# VA-Meter-I2C.net
KiCad netlist of a schematic drawn in EAGLE
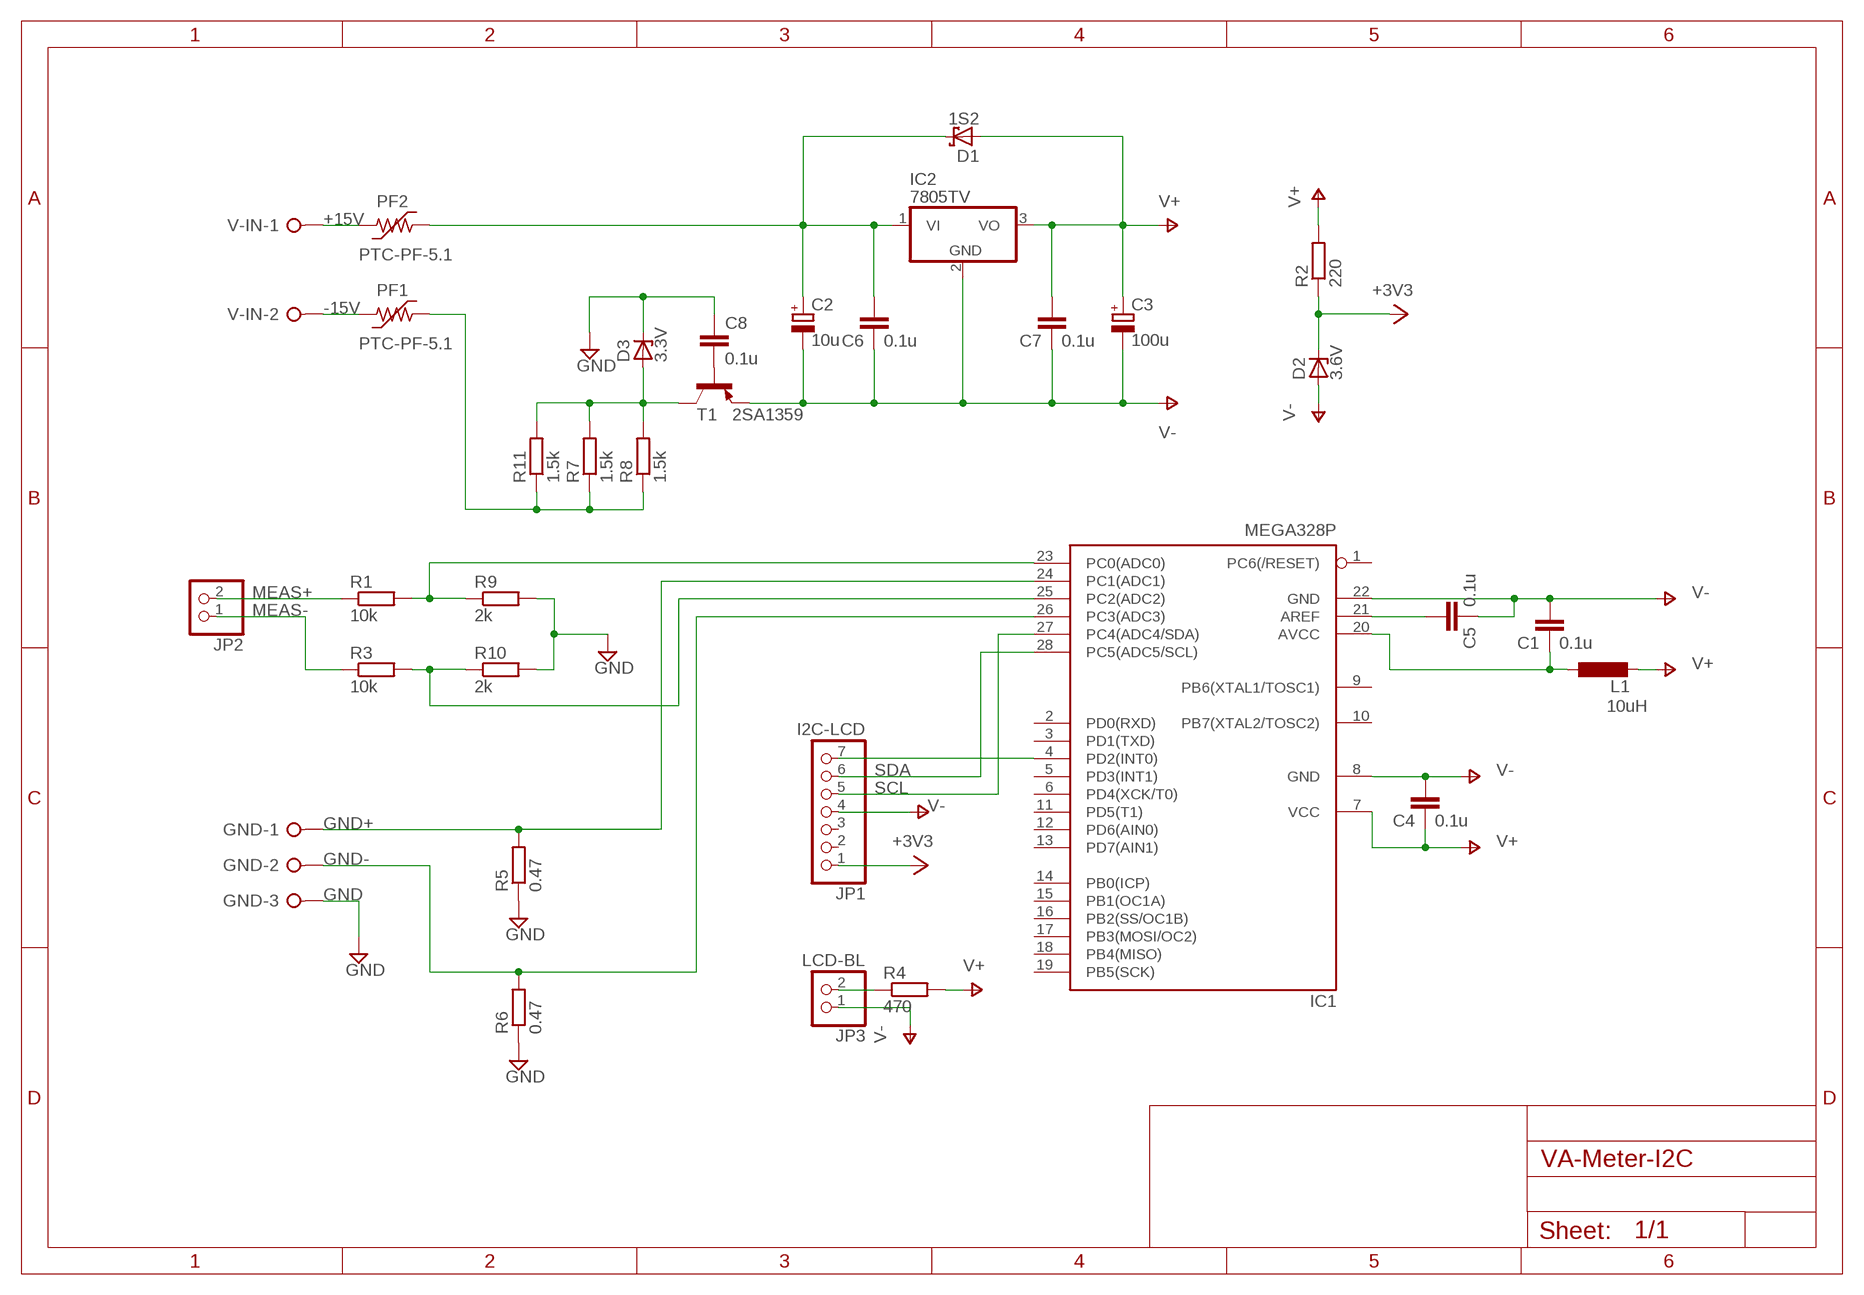
[diagram p0: schematic, sheet 1]

(export (version "E")
  (design (tool "Eeschema 10.0.6"))
  (components
    (comp (ref "C1")
      (value "0.1u")
      (footprint "eagle-import:C050-024X044")
      (libsource (lib "eagle-import") (part "C-EU050-024X044"))
    )
    (comp (ref "C2")
      (value "10u")
      (footprint "eagle-import:E2,5-5")
      (libsource (lib "eagle-import") (part "CPOL-EUE2.5-5"))
    )
    (comp (ref "C3")
      (value "100u")
      (footprint "eagle-import:E2,5-6")
      (libsource (lib "eagle-import") (part "CPOL-EUE2.5-6"))
    )
    (comp (ref "C4")
      (value "0.1u")
      (footprint "eagle-import:C050-024X044")
      (libsource (lib "eagle-import") (part "C-EU050-024X044"))
    )
    (comp (ref "C5")
      (value "0.1u")
      (footprint "eagle-import:C050-024X044")
      (libsource (lib "eagle-import") (part "C-EU050-024X044"))
    )
    (comp (ref "C6")
      (value "0.1u")
      (footprint "eagle-import:C050-024X044")
      (libsource (lib "eagle-import") (part "C-EU050-024X044"))
    )
    (comp (ref "C7")
      (value "0.1u")
      (footprint "eagle-import:C050-024X044")
      (libsource (lib "eagle-import") (part "C-EU050-024X044"))
    )
    (comp (ref "C8")
      (value "0.1u")
      (footprint "eagle-import:C050-024X044")
      (libsource (lib "eagle-import") (part "C-EU050-024X044"))
    )
    (comp (ref "D1")
      (value "1S2")
      (footprint "eagle-import:CB417-15")
      (libsource (lib "eagle-import") (part "SCHOTTKY-DIODECB417-15"))
    )
    (comp (ref "D2")
      (value "3.6V")
      (footprint "eagle-import:ZDIO-5")
      (libsource (lib "eagle-import") (part "ZENER-DIODEZD-5"))
    )
    (comp (ref "D3")
      (value "3.3V")
      (footprint "eagle-import:ZDIO-5")
      (libsource (lib "eagle-import") (part "ZENER-DIODEZD-5"))
    )
    (comp (ref "GND")
      (value "W237-03P")
      (footprint "eagle-import:W237-133")
      (libsource (lib "eagle-import") (part "W237-03P"))
    )
    (comp (ref "IC1")
      (value "MEGA328P")
      (footprint "eagle-import:MEGA328P")
      (libsource (lib "eagle-import") (part "MEGA328P"))
    )
    (comp (ref "IC2")
      (value "7805TV")
      (footprint "eagle-import:TO220V")
      (libsource (lib "eagle-import") (part "78TV05"))
    )
    (comp (ref "JP1")
      (value "I2C-LCD")
      (footprint "eagle-import:1X07")
      (libsource (lib "eagle-import") (part "PINHD-1X7"))
    )
    (comp (ref "JP2")
      (value "PINHD-1X2")
      (footprint "eagle-import:1X02")
      (libsource (lib "eagle-import") (part "PINHD-1X2"))
    )
    (comp (ref "JP3")
      (value "LCD-BL")
      (footprint "eagle-import:1X02")
      (libsource (lib "eagle-import") (part "PINHD-1X2"))
    )
    (comp (ref "L1")
      (value "10uH")
      (footprint "eagle-import:6000-XXXX-RC")
      (libsource (lib "eagle-import") (part "L-EU6000-XXX-RC"))
    )
    (comp (ref "PF1")
      (value "PTC-PF-5.1")
      (footprint "eagle-import:PF-5.1")
      (libsource (lib "eagle-import") (part "PTC-PF-5.1"))
    )
    (comp (ref "PF2")
      (value "PTC-PF-5.1")
      (footprint "eagle-import:PF-5.1")
      (libsource (lib "eagle-import") (part "PTC-PF-5.1"))
    )
    (comp (ref "R1")
      (value "10k")
      (footprint "eagle-import:0207_7")
      (libsource (lib "eagle-import") (part "R-EU_0207/7"))
    )
    (comp (ref "R2")
      (value "220")
      (footprint "eagle-import:0207_7")
      (libsource (lib "eagle-import") (part "R-EU_0207/7"))
    )
    (comp (ref "R3")
      (value "10k")
      (footprint "eagle-import:0207_7")
      (libsource (lib "eagle-import") (part "R-EU_0207/7"))
    )
    (comp (ref "R4")
      (value "470")
      (footprint "eagle-import:0207_7")
      (libsource (lib "eagle-import") (part "R-EU_0207/7"))
    )
    (comp (ref "R5")
      (value "0.47")
      (footprint "eagle-import:P0613_15")
      (libsource (lib "eagle-import") (part "R-EU_0613/15"))
    )
    (comp (ref "R6")
      (value "0.47")
      (footprint "eagle-import:P0613_15")
      (libsource (lib "eagle-import") (part "R-EU_0613/15"))
    )
    (comp (ref "R7")
      (value "1.5k")
      (footprint "eagle-import:P0613_15")
      (libsource (lib "eagle-import") (part "R-EU_0613/15"))
    )
    (comp (ref "R8")
      (value "1.5k")
      (footprint "eagle-import:P0613_15")
      (libsource (lib "eagle-import") (part "R-EU_0613/15"))
    )
    (comp (ref "R9")
      (value "2k")
      (footprint "eagle-import:0207_7")
      (libsource (lib "eagle-import") (part "R-EU_0207/7"))
    )
    (comp (ref "R10")
      (value "2k")
      (footprint "eagle-import:0207_7")
      (libsource (lib "eagle-import") (part "R-EU_0207/7"))
    )
    (comp (ref "R11")
      (value "1.5k")
      (footprint "eagle-import:P0613_15")
      (libsource (lib "eagle-import") (part "R-EU_0613/15"))
    )
    (comp (ref "T1")
      (value "2SA1359")
      (footprint "eagle-import:TO126V")
      (libsource (lib "eagle-import") (part "-PNP-TO126V"))
    )
    (comp (ref "V-IN")
      (value "W237-02P")
      (footprint "eagle-import:W237-132")
      (libsource (lib "eagle-import") (part "W237-02P"))
    )
  )
  (nets
    (net (code "1") (name "+3V3") (class "Default")
      (node (ref "D2") (pin "C") (pinfunction "C_C") (pintype "passive"))
      (node (ref "JP1") (pin "1") (pinfunction "1_1") (pintype "passive"))
      (node (ref "R2") (pin "1") (pinfunction "1_1") (pintype "passive"))
    )
    (net (code "2") (name "/+15V") (class "Default")
      (node (ref "C2") (pin "+") (pinfunction "+_+") (pintype "passive"))
      (node (ref "C6") (pin "2") (pinfunction "2_2") (pintype "passive"))
      (node (ref "D1") (pin "C") (pinfunction "C_C") (pintype "passive"))
      (node (ref "IC2") (pin "1") (pinfunction "VI_1") (pintype "input"))
      (node (ref "PF2") (pin "2") (pinfunction "2_2") (pintype "passive"))
    )
    (net (code "3") (name "/-15V") (class "Default")
      (node (ref "PF1") (pin "2") (pinfunction "2_2") (pintype "passive"))
      (node (ref "R11") (pin "1") (pinfunction "1_1") (pintype "passive"))
      (node (ref "R7") (pin "1") (pinfunction "1_1") (pintype "passive"))
      (node (ref "R8") (pin "1") (pinfunction "1_1") (pintype "passive"))
    )
    (net (code "4") (name "/GND+") (class "Default")
      (node (ref "GND") (pin "1") (pinfunction "KL_1") (pintype "passive"))
      (node (ref "IC1") (pin "24") (pinfunction "PC1(ADC1)_24") (pintype "bidirectional"))
      (node (ref "R5") (pin "2") (pinfunction "2_2") (pintype "passive"))
    )
    (net (code "5") (name "/GND-") (class "Default")
      (node (ref "GND") (pin "2") (pinfunction "KL_2") (pintype "passive"))
      (node (ref "IC1") (pin "26") (pinfunction "PC3(ADC3)_26") (pintype "bidirectional"))
      (node (ref "R6") (pin "2") (pinfunction "2_2") (pintype "passive"))
    )
    (net (code "6") (name "/MEAS+") (class "Default")
      (node (ref "JP2") (pin "2") (pinfunction "2_2") (pintype "passive"))
      (node (ref "R1") (pin "1") (pinfunction "1_1") (pintype "passive"))
    )
    (net (code "7") (name "/MEAS-") (class "Default")
      (node (ref "JP2") (pin "1") (pinfunction "1_1") (pintype "passive"))
      (node (ref "R3") (pin "1") (pinfunction "1_1") (pintype "passive"))
    )
    (net (code "8") (name "/SCL") (class "Default")
      (node (ref "IC1") (pin "27") (pinfunction "PC4(ADC4/SDA)_27") (pintype "bidirectional"))
      (node (ref "JP1") (pin "5") (pinfunction "5_5") (pintype "passive"))
    )
    (net (code "9") (name "/SDA") (class "Default")
      (node (ref "IC1") (pin "28") (pinfunction "PC5(ADC5/SCL)_28") (pintype "bidirectional"))
      (node (ref "JP1") (pin "6") (pinfunction "6_6") (pintype "passive"))
    )
    (net (code "10") (name "GND") (class "Default")
      (node (ref "C8") (pin "1") (pinfunction "1_1") (pintype "passive"))
      (node (ref "D3") (pin "C") (pinfunction "C_C") (pintype "passive"))
      (node (ref "GND") (pin "3") (pinfunction "KL_3") (pintype "passive"))
      (node (ref "R10") (pin "2") (pinfunction "2_2") (pintype "passive"))
      (node (ref "R5") (pin "1") (pinfunction "1_1") (pintype "passive"))
      (node (ref "R6") (pin "1") (pinfunction "1_1") (pintype "passive"))
      (node (ref "R9") (pin "2") (pinfunction "2_2") (pintype "passive"))
    )
    (net (code "11") (name "Net-(IC1-AREF)") (class "Default")
      (node (ref "C5") (pin "2") (pinfunction "2_2") (pintype "passive"))
      (node (ref "IC1") (pin "21") (pinfunction "AREF_21") (pintype "passive"))
    )
    (net (code "12") (name "Net-(IC1-AVCC)") (class "Default")
      (node (ref "C1") (pin "1") (pinfunction "1_1") (pintype "passive"))
      (node (ref "IC1") (pin "20") (pinfunction "AVCC_20") (pintype "power_in"))
      (node (ref "L1") (pin "1") (pinfunction "1_1") (pintype "passive"))
    )
    (net (code "13") (name "Net-(IC1-PC0(ADC0))") (class "Default")
      (node (ref "IC1") (pin "23") (pinfunction "PC0(ADC0)_23") (pintype "bidirectional"))
      (node (ref "R1") (pin "2") (pinfunction "2_2") (pintype "passive"))
      (node (ref "R9") (pin "1") (pinfunction "1_1") (pintype "passive"))
    )
    (net (code "14") (name "Net-(IC1-PC2(ADC2))") (class "Default")
      (node (ref "IC1") (pin "25") (pinfunction "PC2(ADC2)_25") (pintype "bidirectional"))
      (node (ref "R10") (pin "1") (pinfunction "1_1") (pintype "passive"))
      (node (ref "R3") (pin "2") (pinfunction "2_2") (pintype "passive"))
    )
    (net (code "15") (name "Net-(IC1-PD2(INT0))") (class "Default")
      (node (ref "IC1") (pin "4") (pinfunction "PD2(INT0)_4") (pintype "bidirectional"))
      (node (ref "JP1") (pin "7") (pinfunction "7_7") (pintype "passive"))
    )
    (net (code "16") (name "Net-(JP3-Pad2)") (class "Default")
      (node (ref "JP3") (pin "2") (pinfunction "2_2") (pintype "passive"))
      (node (ref "R4") (pin "1") (pinfunction "1_1") (pintype "passive"))
    )
    (net (code "17") (name "Net-(T1-B)") (class "Default")
      (node (ref "C8") (pin "2") (pinfunction "2_2") (pintype "passive"))
      (node (ref "T1") (pin "3") (pinfunction "B_3") (pintype "passive"))
    )
    (net (code "18") (name "Net-(T1-C)") (class "Default")
      (node (ref "D3") (pin "A") (pinfunction "A_A") (pintype "passive"))
      (node (ref "R11") (pin "2") (pinfunction "2_2") (pintype "passive"))
      (node (ref "R7") (pin "2") (pinfunction "2_2") (pintype "passive"))
      (node (ref "R8") (pin "2") (pinfunction "2_2") (pintype "passive"))
      (node (ref "T1") (pin "2") (pinfunction "C_2") (pintype "passive"))
    )
    (net (code "19") (name "Net-(V-INA-KL)") (class "Default")
      (node (ref "PF2") (pin "1") (pinfunction "1_1") (pintype "passive"))
      (node (ref "V-IN") (pin "1") (pinfunction "KL_1") (pintype "passive"))
    )
    (net (code "20") (name "Net-(V-INB-KL)") (class "Default")
      (node (ref "PF1") (pin "1") (pinfunction "1_1") (pintype "passive"))
      (node (ref "V-IN") (pin "2") (pinfunction "KL_2") (pintype "passive"))
    )
    (net (code "21") (name "V+") (class "Default")
      (node (ref "C3") (pin "+") (pinfunction "+_+") (pintype "passive"))
      (node (ref "C4") (pin "1") (pinfunction "1_1") (pintype "passive"))
      (node (ref "C7") (pin "2") (pinfunction "2_2") (pintype "passive"))
      (node (ref "D1") (pin "A") (pinfunction "A_A") (pintype "passive"))
      (node (ref "IC1") (pin "7") (pinfunction "VCC_7") (pintype "power_in"))
      (node (ref "IC2") (pin "3") (pinfunction "VO_3") (pintype "passive"))
      (node (ref "L1") (pin "2") (pinfunction "2_2") (pintype "passive"))
      (node (ref "R2") (pin "2") (pinfunction "2_2") (pintype "passive"))
      (node (ref "R4") (pin "2") (pinfunction "2_2") (pintype "passive"))
    )
    (net (code "22") (name "V-") (class "Default")
      (node (ref "C1") (pin "2") (pinfunction "2_2") (pintype "passive"))
      (node (ref "C2") (pin "-") (pinfunction "-_-") (pintype "passive"))
      (node (ref "C3") (pin "-") (pinfunction "-_-") (pintype "passive"))
      (node (ref "C4") (pin "2") (pinfunction "2_2") (pintype "passive"))
      (node (ref "C5") (pin "1") (pinfunction "1_1") (pintype "passive"))
      (node (ref "C6") (pin "1") (pinfunction "1_1") (pintype "passive"))
      (node (ref "C7") (pin "1") (pinfunction "1_1") (pintype "passive"))
      (node (ref "D2") (pin "A") (pinfunction "A_A") (pintype "passive"))
      (node (ref "IC1") (pin "22") (pinfunction "GND_22") (pintype "power_in"))
      (node (ref "IC1") (pin "8") (pinfunction "GND_8") (pintype "power_in"))
      (node (ref "IC2") (pin "2") (pinfunction "GND_2") (pintype "passive"))
      (node (ref "JP1") (pin "4") (pinfunction "4_4") (pintype "passive"))
      (node (ref "JP3") (pin "1") (pinfunction "1_1") (pintype "passive"))
      (node (ref "T1") (pin "1") (pinfunction "E_1") (pintype "passive"))
    )
    (net (code "23") (name "unconnected-(IC1-PB0(ICP)-Pad14)") (class "Default")
      (node (ref "IC1") (pin "14") (pinfunction "PB0(ICP)_14") (pintype "bidirectional"))
    )
    (net (code "24") (name "unconnected-(IC1-PB1(OC1A)-Pad15)") (class "Default")
      (node (ref "IC1") (pin "15") (pinfunction "PB1(OC1A)_15") (pintype "bidirectional"))
    )
    (net (code "25") (name "unconnected-(IC1-PB2(SS{slash}OC1B)-Pad16)") (class "Default")
      (node (ref "IC1") (pin "16") (pinfunction "PB2(SS/OC1B)_16") (pintype "bidirectional"))
    )
    (net (code "26") (name "unconnected-(IC1-PB3(MOSI{slash}OC2)-Pad17)") (class "Default")
      (node (ref "IC1") (pin "17") (pinfunction "PB3(MOSI/OC2)_17") (pintype "bidirectional"))
    )
    (net (code "27") (name "unconnected-(IC1-PB4(MISO)-Pad18)") (class "Default")
      (node (ref "IC1") (pin "18") (pinfunction "PB4(MISO)_18") (pintype "bidirectional"))
    )
    (net (code "28") (name "unconnected-(IC1-PB5(SCK)-Pad19)") (class "Default")
      (node (ref "IC1") (pin "19") (pinfunction "PB5(SCK)_19") (pintype "bidirectional"))
    )
    (net (code "29") (name "unconnected-(IC1-PB6(XTAL1{slash}TOSC1)-Pad9)") (class "Default")
      (node (ref "IC1") (pin "9") (pinfunction "PB6(XTAL1/TOSC1)_9") (pintype "bidirectional"))
    )
    (net (code "30") (name "unconnected-(IC1-PB7(XTAL2{slash}TOSC2)-Pad10)") (class "Default")
      (node (ref "IC1") (pin "10") (pinfunction "PB7(XTAL2/TOSC2)_10") (pintype "bidirectional"))
    )
    (net (code "31") (name "unconnected-(IC1-PC6({slash}RESET)-Pad1)") (class "Default")
      (node (ref "IC1") (pin "1") (pinfunction "PC6(/RESET)_1") (pintype "bidirectional"))
    )
    (net (code "32") (name "unconnected-(IC1-PD0(RXD)-Pad2)") (class "Default")
      (node (ref "IC1") (pin "2") (pinfunction "PD0(RXD)_2") (pintype "bidirectional"))
    )
    (net (code "33") (name "unconnected-(IC1-PD1(TXD)-Pad3)") (class "Default")
      (node (ref "IC1") (pin "3") (pinfunction "PD1(TXD)_3") (pintype "bidirectional"))
    )
    (net (code "34") (name "unconnected-(IC1-PD3(INT1)-Pad5)") (class "Default")
      (node (ref "IC1") (pin "5") (pinfunction "PD3(INT1)_5") (pintype "bidirectional"))
    )
    (net (code "35") (name "unconnected-(IC1-PD4(XCK{slash}T0)-Pad6)") (class "Default")
      (node (ref "IC1") (pin "6") (pinfunction "PD4(XCK/T0)_6") (pintype "bidirectional"))
    )
    (net (code "36") (name "unconnected-(IC1-PD5(T1)-Pad11)") (class "Default")
      (node (ref "IC1") (pin "11") (pinfunction "PD5(T1)_11") (pintype "bidirectional"))
    )
    (net (code "37") (name "unconnected-(IC1-PD6(AIN0)-Pad12)") (class "Default")
      (node (ref "IC1") (pin "12") (pinfunction "PD6(AIN0)_12") (pintype "bidirectional"))
    )
    (net (code "38") (name "unconnected-(IC1-PD7(AIN1)-Pad13)") (class "Default")
      (node (ref "IC1") (pin "13") (pinfunction "PD7(AIN1)_13") (pintype "bidirectional"))
    )
    (net (code "39") (name "unconnected-(JP1-Pad2)") (class "Default")
      (node (ref "JP1") (pin "2") (pinfunction "2_2") (pintype "passive"))
    )
    (net (code "40") (name "unconnected-(JP1-Pad3)") (class "Default")
      (node (ref "JP1") (pin "3") (pinfunction "3_3") (pintype "passive"))
    )
  )
)
